# SHDN-CURRENT-S10-V00-5kWAlarm.net
KiCad netlist of a schematic drawn in Altium Designer
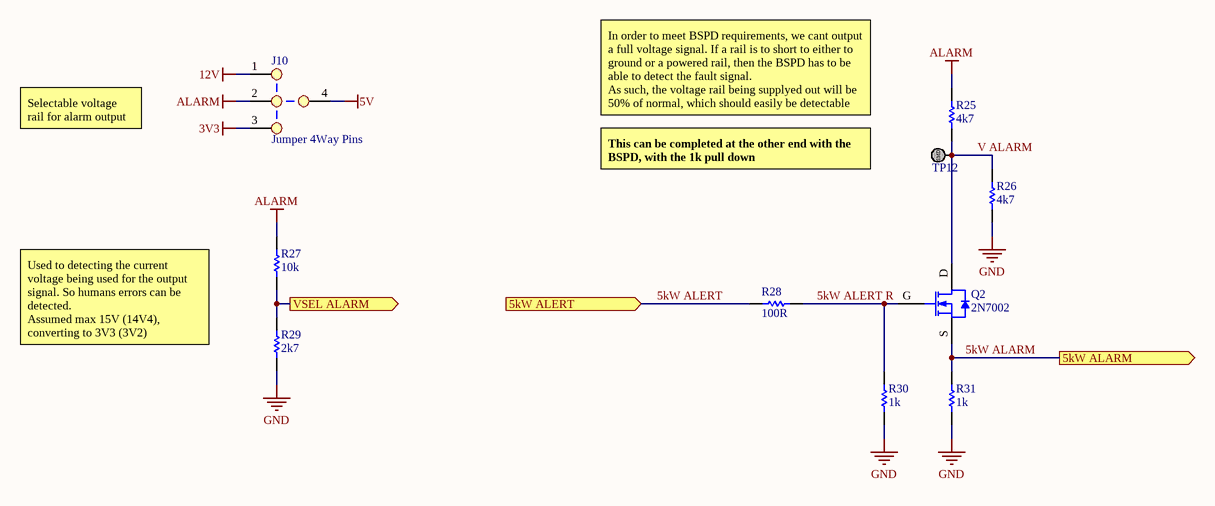
[diagram p0: SHDN-CURRENT-S10-V00-5kWAlarm.SchDoc]

(export (version "E")
  (design (tool "Eeschema 10.0.6"))
  (components
    (comp (ref "J10")
      (value "Jumper 4Way Pins")
      (footprint "Jumper_4Way_Pin")
      (libsource (lib "QUTMS_JumperLibrary") (part "Jumper 4Way Pins"))
    )
    (comp (ref "Q2")
      (value "2N7002")
      (footprint "SOT23-3")
      (libsource (lib "QUTMS_MOSFETLibrary") (part "2N7002"))
    )
    (comp (ref "R25")
      (value "4k7")
      (footprint "Res_ThinFilm_0603")
      (description "Resistor, SMD, 4k7, 0.1W, 5%, 0603")
      (libsource (lib "StandardResistors") (part "4k7 5% 0603"))
    )
    (comp (ref "R26")
      (value "4k7")
      (footprint "Res_ThinFilm_0603")
      (description "Resistor, SMD, 4k7, 0.1W, 5%, 0603")
      (libsource (lib "StandardResistors") (part "4k7 5% 0603"))
    )
    (comp (ref "R27")
      (value "10k")
      (footprint "Res_ThinFilm_0603")
      (description "Resistor, SMD, 10k, 0.1W, 5%, 0603")
      (libsource (lib "StandardResistors") (part "10k 5% 0603"))
    )
    (comp (ref "R28")
      (value "100R")
      (footprint "Res_ThinFilm_0603")
      (description "Resistor, SMD, 100R, 0.1W, 5%, 0603")
      (libsource (lib "StandardResistors") (part "100R 5%, 0603"))
    )
    (comp (ref "R29")
      (value "2k7")
      (footprint "Res_ThinFilm_0603")
      (description "Resistor, SMD, 2k7, 0.1W, 5%, 0603")
      (libsource (lib "StandardResistors") (part "2k7 5% 0603"))
    )
    (comp (ref "R30")
      (value "1k")
      (footprint "Res_ThinFilm_0603")
      (description "Resistor, SMD, 1k, 0.1W, 5%, 0603")
      (libsource (lib "StandardResistors") (part "1k 5% 0603"))
    )
    (comp (ref "R31")
      (value "1k")
      (footprint "Res_ThinFilm_0603")
      (description "Resistor, SMD, 1k, 0.1W, 5%, 0603")
      (libsource (lib "StandardResistors") (part "1k 5% 0603"))
    )
    (comp (ref "TP12")
      (value "TestPoint_SMD")
      (footprint "TestPointSMD")
      (libsource (lib "StandardTest") (part "TestPoint_SMD"))
    )
  )
  (nets
    (net (code "1") (name "/5kW ALARM") (class "Default")
      (node (ref "Q2") (pin "S") (pinfunction "S_S") (pintype "passive"))
      (node (ref "R31") (pin "2") (pinfunction "2_2") (pintype "passive"))
    )
    (net (code "2") (name "/5kW ALERT") (class "Default")
      (node (ref "R28") (pin "1") (pinfunction "1_1") (pintype "passive"))
    )
    (net (code "3") (name "/5kW ALERT R") (class "Default")
      (node (ref "Q2") (pin "G") (pinfunction "G_G") (pintype "passive"))
      (node (ref "R28") (pin "2") (pinfunction "2_2") (pintype "passive"))
      (node (ref "R30") (pin "2") (pinfunction "2_2") (pintype "passive"))
    )
    (net (code "4") (name "/V ALARM") (class "Default")
      (node (ref "Q2") (pin "D") (pinfunction "D_D") (pintype "passive"))
      (node (ref "R25") (pin "1") (pinfunction "1_1") (pintype "passive"))
      (node (ref "R26") (pin "2") (pinfunction "2_2") (pintype "passive"))
      (node (ref "TP12") (pin "1") (pinfunction "1_1") (pintype "passive"))
    )
    (net (code "5") (name "/VSEL ALARM") (class "Default")
      (node (ref "R27") (pin "1") (pinfunction "1_1") (pintype "passive"))
      (node (ref "R29") (pin "2") (pinfunction "2_2") (pintype "passive"))
    )
    (net (code "6") (name "3V3") (class "Default")
      (node (ref "J10") (pin "3") (pinfunction "3_3") (pintype "passive"))
    )
    (net (code "7") (name "5V") (class "Default")
      (node (ref "J10") (pin "4") (pinfunction "4_4") (pintype "passive"))
    )
    (net (code "8") (name "12V") (class "Default")
      (node (ref "J10") (pin "1") (pinfunction "1_1") (pintype "passive"))
    )
    (net (code "9") (name "ALARM") (class "Default")
      (node (ref "J10") (pin "2") (pinfunction "2_2") (pintype "passive"))
      (node (ref "R25") (pin "2") (pinfunction "2_2") (pintype "passive"))
      (node (ref "R27") (pin "2") (pinfunction "2_2") (pintype "passive"))
    )
    (net (code "10") (name "GND") (class "Default")
      (node (ref "R26") (pin "1") (pinfunction "1_1") (pintype "passive"))
      (node (ref "R29") (pin "1") (pinfunction "1_1") (pintype "passive"))
      (node (ref "R30") (pin "1") (pinfunction "1_1") (pintype "passive"))
      (node (ref "R31") (pin "1") (pinfunction "1_1") (pintype "passive"))
    )
  )
)
